# Sheet1.net
KiCad netlist of a schematic drawn in Altium Designer
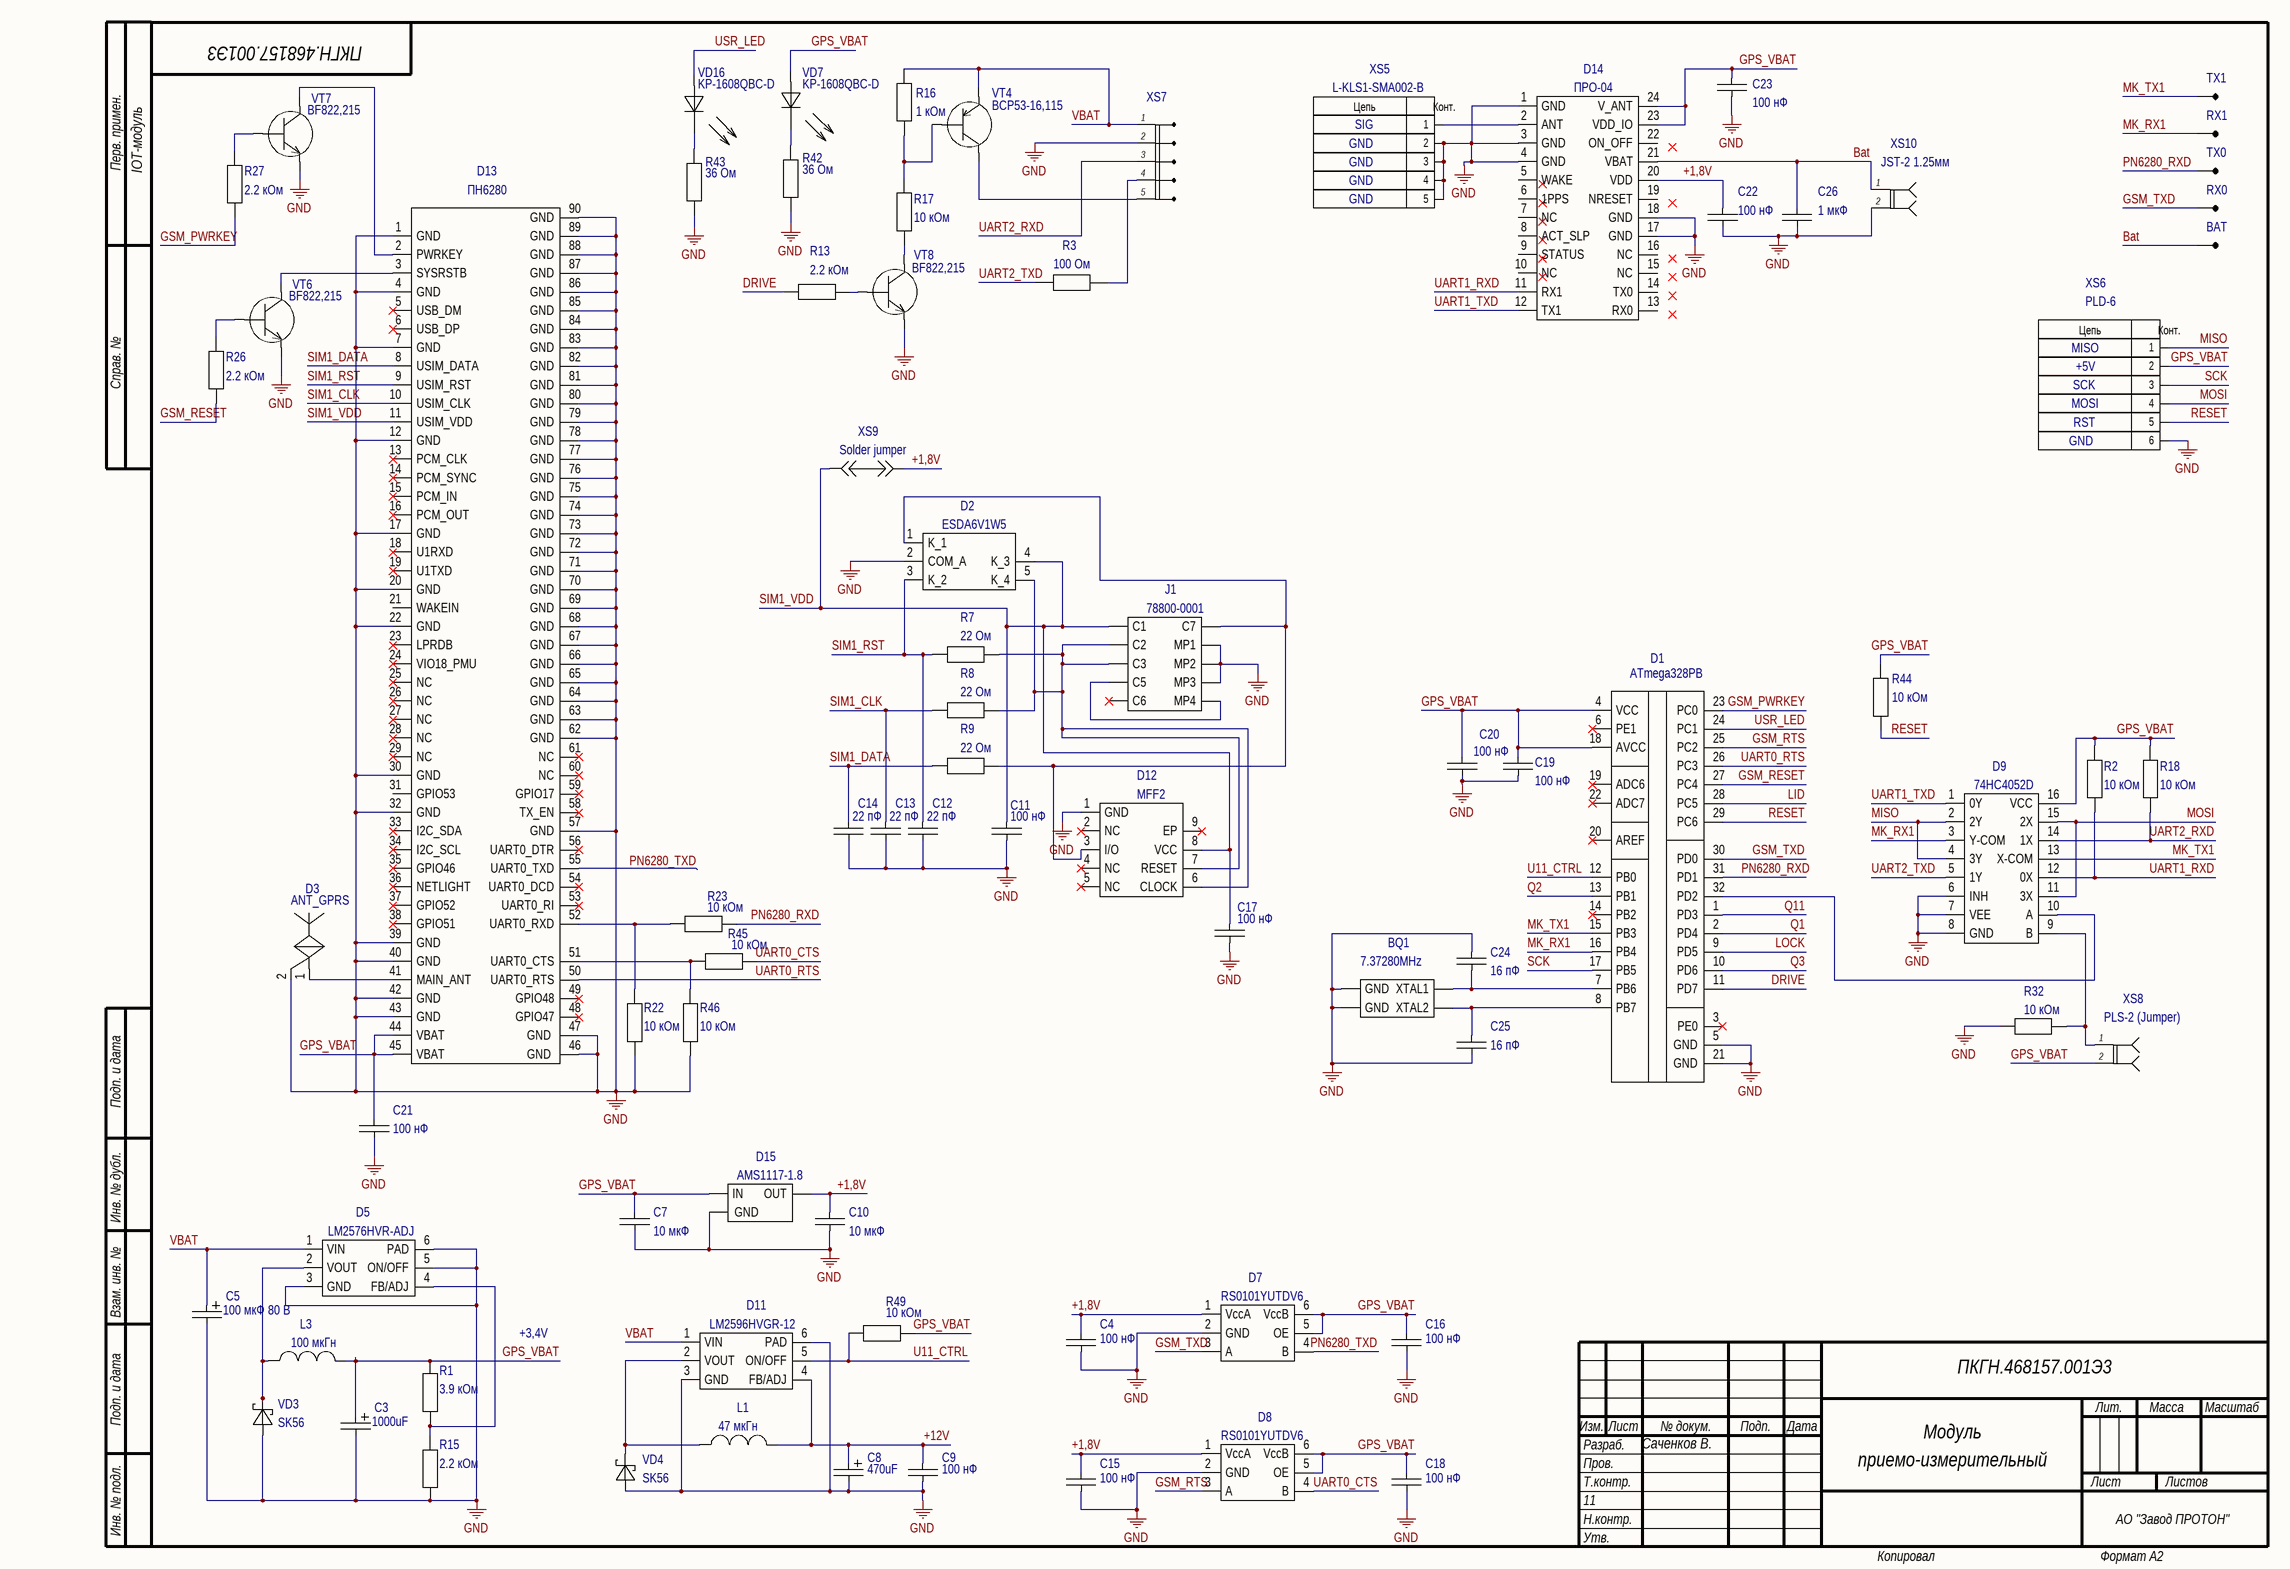
[diagram p0: Sheet1.SchDoc]

(export (version "E")
  (design (tool "Eeschema 10.0.6"))
  (components
    (comp (ref "BAT") (value "Pad") (footprint "PAD") (libsource (lib "Connectors") (part "Pad")))
    (comp (ref "BQ1")
      (value "7.37280MHz")
      (footprint "XTALL_KX-13")
      (description "https://www.elitan.ru/price/item348176")
      (libsource (lib "Own_lib") (part "XTALL_KX-13"))
    )
    (comp (ref "C3")
      (value "1000uF")
      (footprint "Own_lib:CP_SMD_BD10.0-L10.3_W10.3-LS11.0")
      (fields (field (name "TOLERANCE") "20%"))
      (libsource (lib "sch_RU") (part "CapPol"))
    )
    (comp (ref "C4")
      (value "100 нФ")
      (footprint "C_0603_(1608)")
      (fields (field (name "TOLERANCE") "10%"))
      (libsource (lib "sch_RU") (part "Cap"))
    )
    (comp (ref "C5")
      (value "100 мкФ 80 В")
      (footprint "CP_D12.5_H13.5")
      (fields (field (name "TOLERANCE") "20%"))
      (libsource (lib "sch_RU") (part "CapPol"))
    )
    (comp (ref "C7")
      (value "10 мкФ")
      (footprint "C_0603_(1608)")
      (fields (field (name "TOLERANCE") "20%"))
      (libsource (lib "Common_components") (part "C"))
    )
    (comp (ref "C8")
      (value "470uF")
      (footprint "Own_lib:CP_SMD_BD10.0-L10.3_W10.3-LS11.0")
      (fields (field (name "TOLERANCE") "20%"))
      (libsource (lib "sch_RU") (part "CapPol"))
    )
    (comp (ref "C9")
      (value "100 нФ")
      (footprint "C_0603_(1608)")
      (fields (field (name "TOLERANCE") "10%"))
      (libsource (lib "sch_RU") (part "Cap"))
    )
    (comp (ref "C10")
      (value "10 мкФ")
      (footprint "C_0603_(1608)")
      (fields (field (name "TOLERANCE") "20%"))
      (libsource (lib "Common_components") (part "C"))
    )
    (comp (ref "C11")
      (value "100 нФ")
      (footprint "C_0603_(1608)")
      (fields (field (name "TOLERANCE") "10%"))
      (libsource (lib "sch_RU") (part "Cap"))
    )
    (comp (ref "C12")
      (value "22 пФ")
      (footprint "C_0603_(1608)")
      (fields (field (name "TOLERANCE") "5%"))
      (libsource (lib "sch_RU") (part "Cap"))
    )
    (comp (ref "C13")
      (value "22 пФ")
      (footprint "C_0603_(1608)")
      (fields (field (name "TOLERANCE") "5%"))
      (libsource (lib "sch_RU") (part "Cap"))
    )
    (comp (ref "C14")
      (value "22 пФ")
      (footprint "C_0603_(1608)")
      (fields (field (name "TOLERANCE") "5%"))
      (libsource (lib "sch_RU") (part "Cap"))
    )
    (comp (ref "C15")
      (value "100 нФ")
      (footprint "C_0603_(1608)")
      (fields (field (name "TOLERANCE") "10%"))
      (libsource (lib "sch_RU") (part "Cap"))
    )
    (comp (ref "C16")
      (value "100 нФ")
      (footprint "C_0603_(1608)")
      (fields (field (name "TOLERANCE") "10%"))
      (libsource (lib "sch_RU") (part "Cap"))
    )
    (comp (ref "C17")
      (value "100 нФ")
      (footprint "C_0603_(1608)")
      (fields (field (name "TOLERANCE") "10%"))
      (libsource (lib "sch_RU") (part "Cap"))
    )
    (comp (ref "C18")
      (value "100 нФ")
      (footprint "C_0603_(1608)")
      (fields (field (name "TOLERANCE") "10%"))
      (libsource (lib "sch_RU") (part "Cap"))
    )
    (comp (ref "C19")
      (value "100 нФ")
      (footprint "C_0603_(1608)")
      (fields (field (name "TOLERANCE") "10%"))
      (libsource (lib "sch_RU") (part "Cap"))
    )
    (comp (ref "C20")
      (value "100 нФ")
      (footprint "C_0603_(1608)")
      (fields (field (name "TOLERANCE") "10%"))
      (libsource (lib "sch_RU") (part "Cap"))
    )
    (comp (ref "C21")
      (value "100 нФ")
      (footprint "C_0603_(1608)")
      (fields (field (name "TOLERANCE") "10%"))
      (libsource (lib "sch_RU") (part "Cap"))
    )
    (comp (ref "C22")
      (value "100 нФ")
      (footprint "C_0603_(1608)")
      (fields (field (name "TOLERANCE") "10%"))
      (libsource (lib "sch_RU") (part "Cap"))
    )
    (comp (ref "C23")
      (value "100 нФ")
      (footprint "C_0603_(1608)")
      (fields (field (name "TOLERANCE") "10%"))
      (libsource (lib "sch_RU") (part "Cap"))
    )
    (comp (ref "C24")
      (value "16 пФ")
      (footprint "C_0603_(1608)")
      (fields (field (name "TOLERANCE") "5%"))
      (libsource (lib "sch_RU") (part "Cap"))
    )
    (comp (ref "C25")
      (value "16 пФ")
      (footprint "C_0603_(1608)")
      (fields (field (name "TOLERANCE") "5%"))
      (libsource (lib "sch_RU") (part "Cap"))
    )
    (comp (ref "C26")
      (value "1 мкФ")
      (footprint "С_0805_(2012)")
      (fields (field (name "TOLERANCE") "10%"))
      (libsource (lib "sch_RU") (part "Cap"))
    )
    (comp (ref "D1")
      (value "ATmega328PB")
      (footprint "QFP80P900X900X120-32N")
      (libsource (lib "Own_lib") (part "ATmega328PB"))
    )
    (comp (ref "D2")
      (value "ESDA6V1W5")
      (footprint "SamacSys:SOT65P210X110-5N")
      (libsource (lib "Own_lib") (part "ESDA6V1W5"))
    )
    (comp (ref "D3")
      (value "ANT_GPRS")
      (footprint "ANT_GPRS")
      (description "PCB_ant")
      (libsource (lib "Own_lib") (part "ANT_GPRS"))
    )
    (comp (ref "D5")
      (value "LM2576HVR-ADJ")
      (footprint "Own_lib:TO-263-5")
      (libsource (lib "Own_lib") (part "LM2576HVR-ADJ"))
    )
    (comp (ref "D7")
      (value "RS0101YUTDV6")
      (footprint "DFN1.54x1.0-6L")
      (libsource (lib "Own_lib") (part "RS0101YUTDV6"))
    )
    (comp (ref "D8")
      (value "RS0101YUTDV6")
      (footprint "DFN1.54x1.0-6L")
      (libsource (lib "Own_lib") (part "RS0101YUTDV6"))
    )
    (comp (ref "D9")
      (value "74HC4052D")
      (footprint "SOIC127P600X175-16N")
      (libsource (lib "Own_lib") (part "74HC4052D"))
    )
    (comp (ref "D11")
      (value "LM2596HVGR-12")
      (footprint "Own_lib:TO-263-5")
      (libsource (lib "Own_lib") (part "LM2596HVGR-12"))
    )
    (comp (ref "D12")
      (value "MFF2")
      (footprint "SamacSys:SON127P600X500X90-9N-D")
      (libsource (lib "Own_lib") (part "MFF2"))
    )
    (comp (ref "D13")
      (value "ПН6280")
      (footprint "Own_lib:ПН6280")
      (libsource (lib "Own_lib") (part "ПН6280"))
    )
    (comp (ref "D14") (value "ПРО-04") (footprint "PRO-04_SMD") (libsource (lib "Own_lib") (part "PRO-04")))
    (comp (ref "D15")
      (value "AMS1117-1.8")
      (footprint "SOT-223(BCE)")
      (description "https://www.chipdip.ru/product/ams1117-1.8")
      (libsource (lib "Own_lib") (part "AMS1117-3.3"))
    )
    (comp (ref "J1") (value "78800-0001") (libsource (lib "Own_lib") (part "78800")))
    (comp (ref "L1")
      (value "47 мкГн")
      (footprint "Own_lib:B82477G4")
      (libsource (lib "Own_lib") (part "Inductor"))
    )
    (comp (ref "L3")
      (value "100 мкГн")
      (footprint "Own_lib:Inductor_SMD")
      (libsource (lib "Own_lib") (part "Inductor"))
    )
    (comp (ref "R1")
      (value "3.9 кОм")
      (footprint "R_0603_(1608)")
      (fields (field (name "TOLERANCE") "5%"))
      (libsource (lib "Own_lib") (part "R"))
    )
    (comp (ref "R2")
      (value "10 кОм")
      (footprint "R_0603_(1608)")
      (fields (field (name "TOLERANCE") "5%"))
      (libsource (lib "Own_lib") (part "R"))
    )
    (comp (ref "R3")
      (value "100 Ом")
      (footprint "R_0603_(1608)")
      (fields (field (name "TOLERANCE") "5%"))
      (libsource (lib "Common_components") (part "R"))
    )
    (comp (ref "R7")
      (value "22 Ом")
      (footprint "R_0603_(1608)")
      (fields (field (name "TOLERANCE") "5%"))
      (libsource (lib "") (part "R_1"))
    )
    (comp (ref "R8")
      (value "22 Ом")
      (footprint "R_0603_(1608)")
      (fields (field (name "TOLERANCE") "5%"))
      (libsource (lib "") (part "R_1"))
    )
    (comp (ref "R9")
      (value "22 Ом")
      (footprint "R_0603_(1608)")
      (fields (field (name "TOLERANCE") "5%"))
      (libsource (lib "") (part "R_1"))
    )
    (comp (ref "R13")
      (value "2.2 кОм")
      (footprint "R_0603_(1608)")
      (fields (field (name "TOLERANCE") "5%"))
      (libsource (lib "") (part "R_3"))
    )
    (comp (ref "R15")
      (value "2.2 кОм")
      (footprint "R_0603_(1608)")
      (fields (field (name "TOLERANCE") "5%"))
      (libsource (lib "Own_lib") (part "R"))
    )
    (comp (ref "R16")
      (value "1 кОм")
      (footprint "R_0603_(1608)")
      (fields (field (name "TOLERANCE") "5%"))
      (libsource (lib "Own_lib") (part "R"))
    )
    (comp (ref "R17")
      (value "10 кОм")
      (footprint "R_0603_(1608)")
      (fields (field (name "TOLERANCE") "5%"))
      (libsource (lib "Own_lib") (part "R"))
    )
    (comp (ref "R18")
      (value "10 кОм")
      (footprint "R_0603_(1608)")
      (fields (field (name "TOLERANCE") "5%"))
      (libsource (lib "Own_lib") (part "R"))
    )
    (comp (ref "R22")
      (value "10 кОм")
      (footprint "R_0603_(1608)")
      (fields (field (name "TOLERANCE") "5%"))
      (libsource (lib "Own_lib") (part "R"))
    )
    (comp (ref "R23")
      (value "10 кОм")
      (footprint "R_0603_(1608)")
      (fields (field (name "TOLERANCE") "5%"))
      (libsource (lib "") (part "R_1"))
    )
    (comp (ref "R26")
      (value "2.2 кОм")
      (footprint "R_0603_(1608)")
      (fields (field (name "TOLERANCE") "5%"))
      (libsource (lib "Own_lib") (part "R"))
    )
    (comp (ref "R27")
      (value "2.2 кОм")
      (footprint "R_0603_(1608)")
      (fields (field (name "TOLERANCE") "5%"))
      (libsource (lib "Own_lib") (part "R"))
    )
    (comp (ref "R32")
      (value "10 кОм")
      (footprint "R_0603_(1608)")
      (fields (field (name "TOLERANCE") "5%"))
      (libsource (lib "") (part "R_1"))
    )
    (comp (ref "R42")
      (value "36 Ом")
      (footprint "R_0603_(1608)")
      (fields (field (name "TOLERANCE") "5%"))
      (libsource (lib "Own_lib") (part "R"))
    )
    (comp (ref "R43")
      (value "36 Ом")
      (footprint "R_0603_(1608)")
      (fields (field (name "TOLERANCE") "5%"))
      (libsource (lib "Own_lib") (part "R"))
    )
    (comp (ref "R44")
      (value "10 кОм")
      (footprint "R_0603_(1608)")
      (fields (field (name "TOLERANCE") "5%"))
      (libsource (lib "") (part "R_2"))
    )
    (comp (ref "R45")
      (value "10 кОм")
      (footprint "R_0603_(1608)")
      (fields (field (name "TOLERANCE") "5%"))
      (libsource (lib "") (part "R_1"))
    )
    (comp (ref "R46")
      (value "10 кОм")
      (footprint "R_0603_(1608)")
      (fields (field (name "TOLERANCE") "5%"))
      (libsource (lib "Own_lib") (part "R"))
    )
    (comp (ref "R49")
      (value "10 кОм")
      (footprint "R_0603_(1608)")
      (fields (field (name "TOLERANCE") "5%"))
      (libsource (lib "") (part "R_1"))
    )
    (comp (ref "RX0") (value "Pad") (footprint "PAD") (libsource (lib "Connectors") (part "Pad")))
    (comp (ref "RX1") (value "Pad") (footprint "PAD") (libsource (lib "Connectors") (part "Pad")))
    (comp (ref "TX0") (value "Pad") (footprint "PAD") (libsource (lib "Connectors") (part "Pad")))
    (comp (ref "TX1") (value "Pad") (footprint "PAD") (libsource (lib "Connectors") (part "Pad")))
    (comp (ref "VD3")
      (value "SK56")
      (footprint "DIONM5236X261N")
      (description "https://www.chipdip.ru/product/sk56")
      (libsource (lib "sch_RU") (part "Schottky"))
    )
    (comp (ref "VD4")
      (value "SK56")
      (footprint "DIONM5236X261N")
      (description "https://www.chipdip.ru/product/sk56")
      (libsource (lib "sch_RU") (part "Schottky"))
    )
    (comp (ref "VD7")
      (value "KP-1608QBC-D")
      (footprint "SamacSys:KP1608QBCD")
      (libsource (lib "Own_lib") (part "LED"))
    )
    (comp (ref "VD16")
      (value "KP-1608QBC-D")
      (footprint "SamacSys:KP1608QBCD")
      (libsource (lib "Own_lib") (part "LED"))
    )
    (comp (ref "VT4")
      (value "BCP53-16,115")
      (footprint "SOT-223(BCE)")
      (description "https://www.chipdip.ru/product/bcp53-16-nxp")
      (libsource (lib "sch_RU") (part "TRANS-PNP"))
    )
    (comp (ref "VT6")
      (value "BF822,215")
      (footprint "SOT23-3")
      (description "https://www.chipdip.ru/product/bf822-215")
      (libsource (lib "sch_RU") (part "TRANS-NPN"))
    )
    (comp (ref "VT7")
      (value "BF822,215")
      (footprint "SOT23-3")
      (description "https://www.chipdip.ru/product/bf822-215")
      (libsource (lib "sch_RU") (part "TRANS-NPN"))
    )
    (comp (ref "VT8")
      (value "BF822,215")
      (footprint "SOT23-3")
      (description "https://www.chipdip.ru/product/bf822-215")
      (libsource (lib "sch_RU") (part "TRANS-NPN"))
    )
    (comp (ref "XS5")
      (value "L-KLS1-SMA002-B")
      (footprint "LKLS1SMA002B")
      (description "https://www.chipdip.ru/product/kls1-sma002-b-sma-jr")
      (libsource (lib "Own_lib") (part "PLS_5"))
    )
    (comp (ref "XS6")
      (value "PLD-6")
      (footprint "connector:PLD-6")
      (libsource (lib "Own_lib") (part "PLS_6"))
    )
    (comp (ref "XS7")
      (value "Pad 1x5")
      (footprint "PLS-5(NO_3D)")
      (libsource (lib "Connectors") (part "Pad 1x5"))
    )
    (comp (ref "XS8")
      (value "PLS-2 (Jumper)")
      (footprint "PLS-2")
      (libsource (lib "Connectors") (part "XS2"))
    )
    (comp (ref "XS9")
      (value "Solder jumper")
      (footprint "Solder_Jumper")
      (libsource (lib "Own_lib") (part "Jumper_2"))
    )
    (comp (ref "XS10")
      (value "JST-2 1.25мм")
      (footprint "JST-2_1.25")
      (description "https://www.chipdip.ru/product0/9000808758")
      (libsource (lib "Connectors") (part "XS2"))
    )
  )
  (nets
    (net (code "1") (name "/+1,8V") (class "Default")
      (node (ref "C10") (pin "1") (pinfunction "1_1") (pintype "passive"))
      (node (ref "C15") (pin "2") (pinfunction "2_2") (pintype "passive"))
      (node (ref "C22") (pin "2") (pinfunction "2_2") (pintype "passive"))
      (node (ref "C4") (pin "2") (pinfunction "2_2") (pintype "passive"))
      (node (ref "D14") (pin "20") (pinfunction "VDD_20") (pintype "passive"))
      (node (ref "D15") (pin "2") (pinfunction "OUT_2") (pintype "passive"))
      (node (ref "D7") (pin "1") (pinfunction "VccA_1") (pintype "passive"))
      (node (ref "D8") (pin "1") (pinfunction "VccA_1") (pintype "passive"))
      (node (ref "XS9") (pin "2") (pinfunction "2_2") (pintype "passive"))
    )
    (net (code "2") (name "/+12V") (class "Default")
      (node (ref "C8") (pin "1") (pinfunction "1_1") (pintype "passive"))
      (node (ref "C9") (pin "2") (pinfunction "2_2") (pintype "passive"))
      (node (ref "D11") (pin "4") (pinfunction "FB/ADJ_4") (pintype "passive"))
      (node (ref "L1") (pin "2") (pinfunction "2_2") (pintype "passive"))
    )
    (net (code "3") (name "/Bat") (class "Default")
      (node (ref "BAT") (pin "1") (pinfunction "1_1") (pintype "passive"))
      (node (ref "C26") (pin "2") (pinfunction "2_2") (pintype "passive"))
      (node (ref "D14") (pin "21") (pinfunction "VBAT_21") (pintype "passive"))
      (node (ref "XS10") (pin "1") (pinfunction "1_1") (pintype "passive"))
    )
    (net (code "4") (name "/DRIVE") (class "Default")
      (node (ref "D1") (pin "11") (pinfunction "PD7_11") (pintype "passive"))
      (node (ref "R13") (pin "1") (pinfunction "1_1") (pintype "passive"))
    )
    (net (code "5") (name "/GPS_VBAT") (class "Default")
      (node (ref "C16") (pin "2") (pinfunction "2_2") (pintype "passive"))
      (node (ref "C18") (pin "2") (pinfunction "2_2") (pintype "passive"))
      (node (ref "C19") (pin "2") (pinfunction "2_2") (pintype "passive"))
      (node (ref "C20") (pin "2") (pinfunction "2_2") (pintype "passive"))
      (node (ref "C21") (pin "2") (pinfunction "2_2") (pintype "passive"))
      (node (ref "C23") (pin "2") (pinfunction "2_2") (pintype "passive"))
      (node (ref "C3") (pin "1") (pinfunction "1_1") (pintype "passive"))
      (node (ref "C7") (pin "1") (pinfunction "1_1") (pintype "passive"))
      (node (ref "D1") (pin "18") (pinfunction "AVCC_18") (pintype "passive"))
      (node (ref "D1") (pin "4") (pinfunction "VCC_4") (pintype "passive"))
      (node (ref "D13") (pin "44") (pinfunction "VBAT_44") (pintype "passive"))
      (node (ref "D13") (pin "45") (pinfunction "VBAT_45") (pintype "passive"))
      (node (ref "D14") (pin "23") (pinfunction "VDD_IO_23") (pintype "passive"))
      (node (ref "D14") (pin "24") (pinfunction "V_ANT_24") (pintype "passive"))
      (node (ref "D15") (pin "3") (pinfunction "IN_3") (pintype "passive"))
      (node (ref "D7") (pin "5") (pinfunction "OE_5") (pintype "passive"))
      (node (ref "D7") (pin "6") (pinfunction "VccB_6") (pintype "passive"))
      (node (ref "D8") (pin "5") (pinfunction "OE_5") (pintype "passive"))
      (node (ref "D8") (pin "6") (pinfunction "VccB_6") (pintype "passive"))
      (node (ref "D9") (pin "16") (pinfunction "VCC_16") (pintype "passive"))
      (node (ref "L3") (pin "2") (pinfunction "2_2") (pintype "passive"))
      (node (ref "R1") (pin "2") (pinfunction "2_2") (pintype "passive"))
      (node (ref "R18") (pin "2") (pinfunction "2_2") (pintype "passive"))
      (node (ref "R2") (pin "2") (pinfunction "2_2") (pintype "passive"))
      (node (ref "R44") (pin "1") (pinfunction "1_1") (pintype "passive"))
      (node (ref "R49") (pin "1") (pinfunction "1_1") (pintype "passive"))
      (node (ref "VD7") (pin "1") (pinfunction "A_1") (pintype "passive"))
      (node (ref "XS6") (pin "2") (pinfunction "2_2") (pintype "passive"))
      (node (ref "XS8") (pin "2") (pinfunction "2_2") (pintype "passive"))
    )
    (net (code "6") (name "/GSM_PWRKEY") (class "Default")
      (node (ref "D1") (pin "23") (pinfunction "PC0_23") (pintype "passive"))
      (node (ref "R27") (pin "1") (pinfunction "1_1") (pintype "passive"))
    )
    (net (code "7") (name "/GSM_RESET") (class "Default")
      (node (ref "D1") (pin "27") (pinfunction "PC4_27") (pintype "passive"))
      (node (ref "R26") (pin "1") (pinfunction "1_1") (pintype "passive"))
    )
    (net (code "8") (name "/GSM_RTS") (class "Default")
      (node (ref "D1") (pin "25") (pinfunction "PC2_25") (pintype "passive"))
      (node (ref "D8") (pin "3") (pinfunction "A_3") (pintype "passive"))
    )
    (net (code "9") (name "/GSM_TXD") (class "Default")
      (node (ref "D1") (pin "30") (pinfunction "PD0_30") (pintype "passive"))
      (node (ref "D7") (pin "3") (pinfunction "A_3") (pintype "passive"))
      (node (ref "RX0") (pin "1") (pinfunction "1_1") (pintype "passive"))
    )
    (net (code "10") (name "/LID") (class "Default")
      (node (ref "D1") (pin "28") (pinfunction "PC5_28") (pintype "passive"))
    )
    (net (code "11") (name "/LOCK") (class "Default")
      (node (ref "D1") (pin "9") (pinfunction "PD5_9") (pintype "passive"))
    )
    (net (code "12") (name "/MISO") (class "Default")
      (node (ref "D9") (pin "2") (pinfunction "2Y_2") (pintype "passive"))
      (node (ref "D9") (pin "4") (pinfunction "3Y_4") (pintype "passive"))
      (node (ref "XS6") (pin "1") (pinfunction "1_1") (pintype "passive"))
    )
    (net (code "13") (name "/MK_RX1") (class "Default")
      (node (ref "D1") (pin "16") (pinfunction "PB4_16") (pintype "passive"))
      (node (ref "D9") (pin "3") (pinfunction "Y-COM_3") (pintype "passive"))
      (node (ref "RX1") (pin "1") (pinfunction "1_1") (pintype "passive"))
    )
    (net (code "14") (name "/MK_TX1") (class "Default")
      (node (ref "D1") (pin "15") (pinfunction "PB3_15") (pintype "passive"))
      (node (ref "D9") (pin "13") (pinfunction "X-COM_13") (pintype "passive"))
      (node (ref "TX1") (pin "1") (pinfunction "1_1") (pintype "passive"))
    )
    (net (code "15") (name "/MOSI") (class "Default")
      (node (ref "D9") (pin "11") (pinfunction "3X_11") (pintype "passive"))
      (node (ref "D9") (pin "15") (pinfunction "2X_15") (pintype "passive"))
      (node (ref "XS6") (pin "4") (pinfunction "4_4") (pintype "passive"))
    )
    (net (code "16") (name "/PN6280_RXD") (class "Default")
      (node (ref "D1") (pin "31") (pinfunction "PD1_31") (pintype "passive"))
      (node (ref "R23") (pin "1") (pinfunction "1_1") (pintype "passive"))
      (node (ref "TX0") (pin "1") (pinfunction "1_1") (pintype "passive"))
    )
    (net (code "17") (name "/PN6280_TXD") (class "Default")
      (node (ref "D13") (pin "55") (pinfunction "UART0_TXD_55") (pintype "passive"))
      (node (ref "D7") (pin "4") (pinfunction "B_4") (pintype "passive"))
    )
    (net (code "18") (name "/Q1") (class "Default")
      (node (ref "D1") (pin "2") (pinfunction "PD4_2") (pintype "passive"))
    )
    (net (code "19") (name "/Q2") (class "Default")
      (node (ref "D1") (pin "13") (pinfunction "PB1_13") (pintype "passive"))
    )
    (net (code "20") (name "/Q3") (class "Default")
      (node (ref "D1") (pin "10") (pinfunction "PD6_10") (pintype "passive"))
    )
    (net (code "21") (name "/Q11") (class "Default")
      (node (ref "D1") (pin "1") (pinfunction "PD3_1") (pintype "passive"))
    )
    (net (code "22") (name "/RESET") (class "Default")
      (node (ref "D1") (pin "29") (pinfunction "PC6_29") (pintype "passive"))
      (node (ref "R44") (pin "2") (pinfunction "2_2") (pintype "passive"))
      (node (ref "XS6") (pin "5") (pinfunction "5_5") (pintype "passive"))
    )
    (net (code "23") (name "/SCK") (class "Default")
      (node (ref "D1") (pin "17") (pinfunction "PB5_17") (pintype "passive"))
      (node (ref "XS6") (pin "3") (pinfunction "3_3") (pintype "passive"))
    )
    (net (code "24") (name "/SIM1_CLK") (class "Default")
      (node (ref "C13") (pin "2") (pinfunction "2_2") (pintype "passive"))
      (node (ref "D13") (pin "10") (pinfunction "USIM_CLK_10") (pintype "passive"))
      (node (ref "R8") (pin "2") (pinfunction "2_2") (pintype "passive"))
    )
    (net (code "25") (name "/SIM1_DATA") (class "Default")
      (node (ref "C14") (pin "2") (pinfunction "2_2") (pintype "passive"))
      (node (ref "D13") (pin "8") (pinfunction "USIM_DATA_8") (pintype "passive"))
      (node (ref "R9") (pin "2") (pinfunction "2_2") (pintype "passive"))
    )
    (net (code "26") (name "/SIM1_RST") (class "Default")
      (node (ref "C12") (pin "2") (pinfunction "2_2") (pintype "passive"))
      (node (ref "D13") (pin "9") (pinfunction "USIM_RST_9") (pintype "passive"))
      (node (ref "D2") (pin "3") (pinfunction "K_2_3") (pintype "passive"))
      (node (ref "R7") (pin "2") (pinfunction "2_2") (pintype "passive"))
    )
    (net (code "27") (name "/SIM1_VDD") (class "Default")
      (node (ref "C11") (pin "2") (pinfunction "2_2") (pintype "passive"))
      (node (ref "C17") (pin "2") (pinfunction "2_2") (pintype "passive"))
      (node (ref "D12") (pin "8") (pinfunction "VCC_8") (pintype "passive"))
      (node (ref "D13") (pin "11") (pinfunction "USIM_VDD_11") (pintype "passive"))
      (node (ref "D2") (pin "4") (pinfunction "K_3_4") (pintype "passive"))
      (node (ref "J1") (pin "C1") (pinfunction "C1_C1") (pintype "passive"))
      (node (ref "XS9") (pin "1") (pinfunction "1_1") (pintype "passive"))
    )
    (net (code "28") (name "/U11_CTRL") (class "Default")
      (node (ref "D1") (pin "12") (pinfunction "PB0_12") (pintype "passive"))
      (node (ref "D11") (pin "5") (pinfunction "ON/OFF_5") (pintype "passive"))
      (node (ref "R49") (pin "2") (pinfunction "2_2") (pintype "passive"))
    )
    (net (code "29") (name "/UART0_CTS") (class "Default")
      (node (ref "D8") (pin "4") (pinfunction "B_4") (pintype "passive"))
      (node (ref "R45") (pin "1") (pinfunction "1_1") (pintype "passive"))
    )
    (net (code "30") (name "/UART0_RTS") (class "Default")
      (node (ref "D1") (pin "26") (pinfunction "PC3_26") (pintype "passive"))
      (node (ref "D13") (pin "50") (pinfunction "UART0_RTS_50") (pintype "passive"))
    )
    (net (code "31") (name "/UART1_RXD") (class "Default")
      (node (ref "D14") (pin "11") (pinfunction "RX1_11") (pintype "passive"))
      (node (ref "D9") (pin "12") (pinfunction "0X_12") (pintype "passive"))
      (node (ref "R2") (pin "1") (pinfunction "1_1") (pintype "passive"))
    )
    (net (code "32") (name "/UART1_TXD") (class "Default")
      (node (ref "D14") (pin "12") (pinfunction "TX1_12") (pintype "passive"))
      (node (ref "D9") (pin "1") (pinfunction "0Y_1") (pintype "passive"))
    )
    (net (code "33") (name "/UART2_RXD") (class "Default")
      (node (ref "D9") (pin "14") (pinfunction "1X_14") (pintype "passive"))
      (node (ref "R18") (pin "1") (pinfunction "1_1") (pintype "passive"))
      (node (ref "XS7") (pin "3") (pinfunction "3_3") (pintype "passive"))
    )
    (net (code "34") (name "/UART2_TXD") (class "Default")
      (node (ref "D9") (pin "5") (pinfunction "1Y_5") (pintype "passive"))
      (node (ref "R3") (pin "1") (pinfunction "1_1") (pintype "passive"))
    )
    (net (code "35") (name "/USR_LED") (class "Default")
      (node (ref "D1") (pin "24") (pinfunction "PC1_24") (pintype "passive"))
      (node (ref "VD16") (pin "1") (pinfunction "A_1") (pintype "passive"))
    )
    (net (code "36") (name "/VBAT") (class "Default")
      (node (ref "C5") (pin "1") (pinfunction "1_1") (pintype "passive"))
      (node (ref "D11") (pin "1") (pinfunction "VIN_1") (pintype "passive"))
      (node (ref "D5") (pin "1") (pinfunction "VIN_1") (pintype "passive"))
      (node (ref "R16") (pin "2") (pinfunction "2_2") (pintype "passive"))
      (node (ref "VT4") (pin "3") (pinfunction "E_3") (pintype "passive"))
      (node (ref "XS7") (pin "1") (pinfunction "1_1") (pintype "passive"))
    )
    (net (code "37") (name "GND") (class "Default")
      (node (ref "BQ1") (pin "2") (pinfunction "GND_2") (pintype "passive"))
      (node (ref "BQ1") (pin "4") (pinfunction "GND_4") (pintype "passive"))
      (node (ref "C10") (pin "2") (pinfunction "2_2") (pintype "passive"))
      (node (ref "C11") (pin "1") (pinfunction "1_1") (pintype "passive"))
      (node (ref "C12") (pin "1") (pinfunction "1_1") (pintype "passive"))
      (node (ref "C13") (pin "1") (pinfunction "1_1") (pintype "passive"))
      (node (ref "C14") (pin "1") (pinfunction "1_1") (pintype "passive"))
      (node (ref "C15") (pin "1") (pinfunction "1_1") (pintype "passive"))
      (node (ref "C16") (pin "1") (pinfunction "1_1") (pintype "passive"))
      (node (ref "C17") (pin "1") (pinfunction "1_1") (pintype "passive"))
      (node (ref "C18") (pin "1") (pinfunction "1_1") (pintype "passive"))
      (node (ref "C19") (pin "1") (pinfunction "1_1") (pintype "passive"))
      (node (ref "C20") (pin "1") (pinfunction "1_1") (pintype "passive"))
      (node (ref "C21") (pin "1") (pinfunction "1_1") (pintype "passive"))
      (node (ref "C22") (pin "1") (pinfunction "1_1") (pintype "passive"))
      (node (ref "C23") (pin "1") (pinfunction "1_1") (pintype "passive"))
      (node (ref "C24") (pin "2") (pinfunction "2_2") (pintype "passive"))
      (node (ref "C25") (pin "1") (pinfunction "1_1") (pintype "passive"))
      (node (ref "C26") (pin "1") (pinfunction "1_1") (pintype "passive"))
      (node (ref "C3") (pin "2") (pinfunction "2_2") (pintype "passive"))
      (node (ref "C4") (pin "1") (pinfunction "1_1") (pintype "passive"))
      (node (ref "C5") (pin "2") (pinfunction "2_2") (pintype "passive"))
      (node (ref "C7") (pin "2") (pinfunction "2_2") (pintype "passive"))
      (node (ref "C8") (pin "2") (pinfunction "2_2") (pintype "passive"))
      (node (ref "C9") (pin "1") (pinfunction "1_1") (pintype "passive"))
      (node (ref "D1") (pin "21") (pinfunction "GND_21") (pintype "passive"))
      (node (ref "D1") (pin "5") (pinfunction "GND_5") (pintype "passive"))
      (node (ref "D11") (pin "3") (pinfunction "GND_3") (pintype "passive"))
      (node (ref "D11") (pin "6") (pinfunction "PAD_6") (pintype "passive"))
      (node (ref "D12") (pin "1") (pinfunction "GND_1") (pintype "passive"))
      (node (ref "D13") (pin "1") (pinfunction "GND_1") (pintype "passive"))
      (node (ref "D13") (pin "12") (pinfunction "GND_12") (pintype "passive"))
      (node (ref "D13") (pin "17") (pinfunction "GND_17") (pintype "passive"))
      (node (ref "D13") (pin "20") (pinfunction "GND_20") (pintype "passive"))
      (node (ref "D13") (pin "22") (pinfunction "GND_22") (pintype "passive"))
      (node (ref "D13") (pin "30") (pinfunction "GND_30") (pintype "passive"))
      (node (ref "D13") (pin "32") (pinfunction "GND_32") (pintype "passive"))
      (node (ref "D13") (pin "39") (pinfunction "GND_39") (pintype "passive"))
      (node (ref "D13") (pin "4") (pinfunction "GND_4") (pintype "passive"))
      (node (ref "D13") (pin "40") (pinfunction "GND_40") (pintype "passive"))
      (node (ref "D13") (pin "42") (pinfunction "GND_42") (pintype "passive"))
      (node (ref "D13") (pin "43") (pinfunction "GND_43") (pintype "passive"))
      (node (ref "D13") (pin "46") (pinfunction "GND_46") (pintype "passive"))
      (node (ref "D13") (pin "47") (pinfunction "GND_47") (pintype "passive"))
      (node (ref "D13") (pin "57") (pinfunction "GND_57") (pintype "passive"))
      (node (ref "D13") (pin "62") (pinfunction "GND_62") (pintype "passive"))
      (node (ref "D13") (pin "63") (pinfunction "GND_63") (pintype "passive"))
      (node (ref "D13") (pin "64") (pinfunction "GND_64") (pintype "passive"))
      (node (ref "D13") (pin "65") (pinfunction "GND_65") (pintype "passive"))
      (node (ref "D13") (pin "66") (pinfunction "GND_66") (pintype "passive"))
      (node (ref "D13") (pin "67") (pinfunction "GND_67") (pintype "passive"))
      (node (ref "D13") (pin "68") (pinfunction "GND_68") (pintype "passive"))
      (node (ref "D13") (pin "69") (pinfunction "GND_69") (pintype "passive"))
      (node (ref "D13") (pin "7") (pinfunction "GND_7") (pintype "passive"))
      (node (ref "D13") (pin "70") (pinfunction "GND_70") (pintype "passive"))
      (node (ref "D13") (pin "71") (pinfunction "GND_71") (pintype "passive"))
      (node (ref "D13") (pin "72") (pinfunction "GND_72") (pintype "passive"))
      (node (ref "D13") (pin "73") (pinfunction "GND_73") (pintype "passive"))
      (node (ref "D13") (pin "74") (pinfunction "GND_74") (pintype "passive"))
      (node (ref "D13") (pin "75") (pinfunction "GND_75") (pintype "passive"))
      (node (ref "D13") (pin "76") (pinfunction "GND_76") (pintype "passive"))
      (node (ref "D13") (pin "77") (pinfunction "GND_77") (pintype "passive"))
      (node (ref "D13") (pin "78") (pinfunction "GND_78") (pintype "passive"))
      (node (ref "D13") (pin "79") (pinfunction "GND_79") (pintype "passive"))
      (node (ref "D13") (pin "80") (pinfunction "GND_80") (pintype "passive"))
      (node (ref "D13") (pin "81") (pinfunction "GND_81") (pintype "passive"))
      (node (ref "D13") (pin "82") (pinfunction "GND_82") (pintype "passive"))
      (node (ref "D13") (pin "83") (pinfunction "GND_83") (pintype "passive"))
      (node (ref "D13") (pin "84") (pinfunction "GND_84") (pintype "passive"))
      (node (ref "D13") (pin "85") (pinfunction "GND_85") (pintype "passive"))
      (node (ref "D13") (pin "86") (pinfunction "GND_86") (pintype "passive"))
      (node (ref "D13") (pin "87") (pinfunction "GND_87") (pintype "passive"))
      (node (ref "D13") (pin "88") (pinfunction "GND_88") (pintype "passive"))
      (node (ref "D13") (pin "89") (pinfunction "GND_89") (pintype "passive"))
      (node (ref "D13") (pin "90") (pinfunction "GND_90") (pintype "passive"))
      (node (ref "D14") (pin "1") (pinfunction "GND_1") (pintype "passive"))
      (node (ref "D14") (pin "17") (pinfunction "GND_17") (pintype "passive"))
      (node (ref "D14") (pin "18") (pinfunction "GND_18") (pintype "passive"))
      (node (ref "D14") (pin "3") (pinfunction "GND_3") (pintype "passive"))
      (node (ref "D14") (pin "4") (pinfunction "GND_4") (pintype "passive"))
      (node (ref "D15") (pin "1") (pinfunction "GND_1") (pintype "passive"))
      (node (ref "D2") (pin "2") (pinfunction "COM_A_2") (pintype "passive"))
      (node (ref "D3") (pin "2") (pinfunction "GND_2") (pintype "passive"))
      (node (ref "D5") (pin "3") (pinfunction "GND_3") (pintype "passive"))
      (node (ref "D5") (pin "5") (pinfunction "ON/OFF_5") (pintype "passive"))
      (node (ref "D5") (pin "6") (pinfunction "PAD_6") (pintype "passive"))
      (node (ref "D7") (pin "2") (pinfunction "GND_2") (pintype "passive"))
      (node (ref "D8") (pin "2") (pinfunction "GND_2") (pintype "passive"))
      (node (ref "D9") (pin "6") (pinfunction "INH_6") (pintype "passive"))
      (node (ref "D9") (pin "7") (pinfunction "VEE_7") (pintype "passive"))
      (node (ref "D9") (pin "8") (pinfunction "GND_8") (pintype "passive"))
      (node (ref "J1") (pin "MP1") (pinfunction "MP1_MP1") (pintype "passive"))
      (node (ref "J1") (pin "MP2") (pinfunction "MP2_MP2") (pintype "passive"))
      (node (ref "J1") (pin "MP3") (pinfunction "MP3_MP3") (pintype "passive"))
      (node (ref "R15") (pin "1") (pinfunction "1_1") (pintype "passive"))
      (node (ref "R22") (pin "1") (pinfunction "1_1") (pintype "passive"))
      (node (ref "R32") (pin "2") (pinfunction "2_2") (pintype "passive"))
      (node (ref "R42") (pin "1") (pinfunction "1_1") (pintype "passive"))
      (node (ref "R43") (pin "1") (pinfunction "1_1") (pintype "passive"))
      (node (ref "R46") (pin "1") (pinfunction "1_1") (pintype "passive"))
      (node (ref "VD3") (pin "2") (pinfunction "2_2") (pintype "passive"))
      (node (ref "VD4") (pin "2") (pinfunction "2_2") (pintype "passive"))
      (node (ref "VT6") (pin "2") (pinfunction "E_2") (pintype "passive"))
      (node (ref "VT7") (pin "2") (pinfunction "E_2") (pintype "passive"))
      (node (ref "VT8") (pin "2") (pinfunction "E_2") (pintype "passive"))
      (node (ref "XS10") (pin "2") (pinfunction "2_2") (pintype "passive"))
      (node (ref "XS5") (pin "2") (pinfunction "2_2") (pintype "passive"))
      (node (ref "XS5") (pin "3") (pinfunction "3_3") (pintype "passive"))
      (node (ref "XS5") (pin "4") (pinfunction "4_4") (pintype "passive"))
      (node (ref "XS5") (pin "5") (pinfunction "5_5") (pintype "passive"))
      (node (ref "XS6") (pin "6") (pinfunction "6_6") (pintype "passive"))
      (node (ref "XS7") (pin "2") (pinfunction "2_2") (pintype "passive"))
    )
    (net (code "38") (name "Net-(BQ1-XTAL1)") (class "Default")
      (node (ref "BQ1") (pin "1") (pinfunction "XTAL1_1") (pintype "passive"))
      (node (ref "C24") (pin "1") (pinfunction "1_1") (pintype "passive"))
      (node (ref "D1") (pin "7") (pinfunction "PB6_7") (pintype "passive"))
    )
    (net (code "39") (name "Net-(BQ1-XTAL2)") (class "Default")
      (node (ref "BQ1") (pin "3") (pinfunction "XTAL2_3") (pintype "passive"))
      (node (ref "C25") (pin "2") (pinfunction "2_2") (pintype "passive"))
      (node (ref "D1") (pin "8") (pinfunction "PB7_8") (pintype "passive"))
    )
    (net (code "40") (name "Net-(D1-PD2)") (class "Default")
      (node (ref "D1") (pin "32") (pinfunction "PD2_32") (pintype "passive"))
      (node (ref "D9") (pin "10") (pinfunction "A_10") (pintype "passive"))
    )
    (net (code "41") (name "Net-(D5-FB{slash}ADJ)") (class "Default")
      (node (ref "D5") (pin "4") (pinfunction "FB/ADJ_4") (pintype "passive"))
      (node (ref "R1") (pin "1") (pinfunction "1_1") (pintype "passive"))
      (node (ref "R15") (pin "2") (pinfunction "2_2") (pintype "passive"))
    )
    (net (code "42") (name "Net-(D5-VOUT)") (class "Default")
      (node (ref "D5") (pin "2") (pinfunction "VOUT_2") (pintype "passive"))
      (node (ref "L3") (pin "1") (pinfunction "1_1") (pintype "passive"))
      (node (ref "VD3") (pin "1") (pinfunction "1_1") (pintype "passive"))
    )
    (net (code "43") (name "Net-(D9-B)") (class "Default")
      (node (ref "D9") (pin "9") (pinfunction "B_9") (pintype "passive"))
      (node (ref "R32") (pin "1") (pinfunction "1_1") (pintype "passive"))
      (node (ref "XS8") (pin "1") (pinfunction "1_1") (pintype "passive"))
    )
    (net (code "44") (name "Net-(D11-VOUT)") (class "Default")
      (node (ref "D11") (pin "2") (pinfunction "VOUT_2") (pintype "passive"))
      (node (ref "L1") (pin "1") (pinfunction "1_1") (pintype "passive"))
      (node (ref "VD4") (pin "1") (pinfunction "1_1") (pintype "passive"))
    )
    (net (code "45") (name "Net-(D12-CLOCK)") (class "Default")
      (node (ref "D12") (pin "6") (pinfunction "CLOCK_6") (pintype "passive"))
      (node (ref "D12") (pin "7") (pinfunction "RESET_7") (pintype "passive"))
      (node (ref "D2") (pin "5") (pinfunction "K_4_5") (pintype "passive"))
      (node (ref "J1") (pin "C2") (pinfunction "C2_C2") (pintype "passive"))
      (node (ref "J1") (pin "C3") (pinfunction "C3_C3") (pintype "passive"))
      (node (ref "R7") (pin "1") (pinfunction "1_1") (pintype "passive"))
      (node (ref "R8") (pin "1") (pinfunction "1_1") (pintype "passive"))
    )
    (net (code "46") (name "Net-(D12-I{slash}O)") (class "Default")
      (node (ref "D12") (pin "3") (pinfunction "I/O_3") (pintype "passive"))
      (node (ref "D2") (pin "1") (pinfunction "K_1_1") (pintype "passive"))
      (node (ref "J1") (pin "C7") (pinfunction "C7_C7") (pintype "passive"))
      (node (ref "R9") (pin "1") (pinfunction "1_1") (pintype "passive"))
    )
    (net (code "47") (name "Net-(D13-MAIN_ANT)") (class "Default")
      (node (ref "D13") (pin "41") (pinfunction "MAIN_ANT_41") (pintype "passive"))
      (node (ref "D3") (pin "1") (pinfunction "NET_1") (pintype "passive"))
    )
    (net (code "48") (name "Net-(D13-PWRKEY)") (class "Default")
      (node (ref "D13") (pin "2") (pinfunction "PWRKEY_2") (pintype "passive"))
      (node (ref "VT7") (pin "3") (pinfunction "C_3") (pintype "passive"))
    )
    (net (code "49") (name "Net-(D13-SYSRSTB)") (class "Default")
      (node (ref "D13") (pin "3") (pinfunction "SYSRSTB_3") (pintype "passive"))
      (node (ref "VT6") (pin "3") (pinfunction "C_3") (pintype "passive"))
    )
    (net (code "50") (name "Net-(D13-UART0_CTS)") (class "Default")
      (node (ref "D13") (pin "51") (pinfunction "UART0_CTS_51") (pintype "passive"))
      (node (ref "R45") (pin "2") (pinfunction "2_2") (pintype "passive"))
      (node (ref "R46") (pin "2") (pinfunction "2_2") (pintype "passive"))
    )
    (net (code "51") (name "Net-(D13-UART0_RXD)") (class "Default")
      (node (ref "D13") (pin "52") (pinfunction "UART0_RXD_52") (pintype "passive"))
      (node (ref "R22") (pin "2") (pinfunction "2_2") (pintype "passive"))
      (node (ref "R23") (pin "2") (pinfunction "2_2") (pintype "passive"))
    )
    (net (code "52") (name "Net-(D14-ANT)") (class "Default")
      (node (ref "D14") (pin "2") (pinfunction "ANT_2") (pintype "passive"))
      (node (ref "XS5") (pin "1") (pinfunction "1_1") (pintype "passive"))
    )
    (net (code "53") (name "Net-(J1-PadC5)") (class "Default")
      (node (ref "J1") (pin "C5") (pinfunction "C5_C5") (pintype "passive"))
      (node (ref "J1") (pin "MP4") (pinfunction "MP4_MP4") (pintype "passive"))
    )
    (net (code "54") (name "Net-(R3-Pad2)") (class "Default")
      (node (ref "R3") (pin "2") (pinfunction "2_2") (pintype "passive"))
      (node (ref "XS7") (pin "4") (pinfunction "4_4") (pintype "passive"))
    )
    (net (code "55") (name "Net-(VD7-C)") (class "Default")
      (node (ref "R42") (pin "2") (pinfunction "2_2") (pintype "passive"))
      (node (ref "VD7") (pin "2") (pinfunction "C_2") (pintype "passive"))
    )
    (net (code "56") (name "Net-(VD16-C)") (class "Default")
      (node (ref "R43") (pin "2") (pinfunction "2_2") (pintype "passive"))
      (node (ref "VD16") (pin "2") (pinfunction "C_2") (pintype "passive"))
    )
    (net (code "57") (name "Net-(VT4-B)") (class "Default")
      (node (ref "R16") (pin "1") (pinfunction "1_1") (pintype "passive"))
      (node (ref "R17") (pin "2") (pinfunction "2_2") (pintype "passive"))
      (node (ref "VT4") (pin "1") (pinfunction "B_1") (pintype "passive"))
    )
    (net (code "58") (name "Net-(VT4-C)") (class "Default")
      (node (ref "VT4") (pin "2") (pinfunction "C_2") (pintype "passive"))
      (node (ref "XS7") (pin "5") (pinfunction "5_5") (pintype "passive"))
    )
    (net (code "59") (name "Net-(VT6-B)") (class "Default")
      (node (ref "R26") (pin "2") (pinfunction "2_2") (pintype "passive"))
      (node (ref "VT6") (pin "1") (pinfunction "B_1") (pintype "passive"))
    )
    (net (code "60") (name "Net-(VT7-B)") (class "Default")
      (node (ref "R27") (pin "2") (pinfunction "2_2") (pintype "passive"))
      (node (ref "VT7") (pin "1") (pinfunction "B_1") (pintype "passive"))
    )
    (net (code "61") (name "Net-(VT8-B)") (class "Default")
      (node (ref "R13") (pin "2") (pinfunction "2_2") (pintype "passive"))
      (node (ref "VT8") (pin "1") (pinfunction "B_1") (pintype "passive"))
    )
    (net (code "62") (name "Net-(VT8-C)") (class "Default")
      (node (ref "R17") (pin "1") (pinfunction "1_1") (pintype "passive"))
      (node (ref "VT8") (pin "3") (pinfunction "C_3") (pintype "passive"))
    )
    (net (code "63") (name "unconnected-(D1-ADC6-Pad19)") (class "Default")
      (node (ref "D1") (pin "19") (pinfunction "ADC6_19") (pintype "passive+no_connect"))
    )
    (net (code "64") (name "unconnected-(D1-ADC7-Pad22)") (class "Default")
      (node (ref "D1") (pin "22") (pinfunction "ADC7_22") (pintype "passive+no_connect"))
    )
    (net (code "65") (name "unconnected-(D1-AREF-Pad20)") (class "Default")
      (node (ref "D1") (pin "20") (pinfunction "AREF_20") (pintype "passive+no_connect"))
    )
    (net (code "66") (name "unconnected-(D1-PB2-Pad14)") (class "Default")
      (node (ref "D1") (pin "14") (pinfunction "PB2_14") (pintype "passive+no_connect"))
    )
    (net (code "67") (name "unconnected-(D1-PE0-Pad3)") (class "Default")
      (node (ref "D1") (pin "3") (pinfunction "PE0_3") (pintype "passive+no_connect"))
    )
    (net (code "68") (name "unconnected-(D1-PE1-Pad6)") (class "Default")
      (node (ref "D1") (pin "6") (pinfunction "PE1_6") (pintype "passive+no_connect"))
    )
    (net (code "69") (name "unconnected-(D12-EP-Pad9)") (class "Default")
      (node (ref "D12") (pin "9") (pinfunction "EP_9") (pintype "passive+no_connect"))
    )
    (net (code "70") (name "unconnected-(D12-NC-Pad2)") (class "Default")
      (node (ref "D12") (pin "2") (pinfunction "NC_2") (pintype "passive+no_connect"))
    )
    (net (code "71") (name "unconnected-(D12-NC-Pad4)") (class "Default")
      (node (ref "D12") (pin "4") (pinfunction "NC_4") (pintype "passive+no_connect"))
    )
    (net (code "72") (name "unconnected-(D12-NC-Pad5)") (class "Default")
      (node (ref "D12") (pin "5") (pinfunction "NC_5") (pintype "passive+no_connect"))
    )
    (net (code "73") (name "unconnected-(D13-GPIO17-Pad59)") (class "Default")
      (node (ref "D13") (pin "59") (pinfunction "GPIO17_59") (pintype "passive+no_connect"))
    )
    (net (code "74") (name "unconnected-(D13-GPIO46-Pad35)") (class "Default")
      (node (ref "D13") (pin "35") (pinfunction "GPIO46_35") (pintype "passive+no_connect"))
    )
    (net (code "75") (name "unconnected-(D13-GPIO47-Pad48)") (class "Default")
      (node (ref "D13") (pin "48") (pinfunction "GPIO47_48") (pintype "passive+no_connect"))
    )
    (net (code "76") (name "unconnected-(D13-GPIO48-Pad49)") (class "Default")
      (node (ref "D13") (pin "49") (pinfunction "GPIO48_49") (pintype "passive+no_connect"))
    )
    (net (code "77") (name "unconnected-(D13-GPIO51-Pad38)") (class "Default")
      (node (ref "D13") (pin "38") (pinfunction "GPIO51_38") (pintype "passive+no_connect"))
    )
    (net (code "78") (name "unconnected-(D13-GPIO52-Pad37)") (class "Default")
      (node (ref "D13") (pin "37") (pinfunction "GPIO52_37") (pintype "passive+no_connect"))
    )
    (net (code "79") (name "unconnected-(D13-GPIO53-Pad31)") (class "Default")
      (node (ref "D13") (pin "31") (pinfunction "GPIO53_31") (pintype "passive"))
    )
    (net (code "80") (name "unconnected-(D13-I2C_SCL-Pad34)") (class "Default")
      (node (ref "D13") (pin "34") (pinfunction "I2C_SCL_34") (pintype "passive+no_connect"))
    )
    (net (code "81") (name "unconnected-(D13-I2C_SDA-Pad33)") (class "Default")
      (node (ref "D13") (pin "33") (pinfunction "I2C_SDA_33") (pintype "passive+no_connect"))
    )
    (net (code "82") (name "unconnected-(D13-LPRDB-Pad23)") (class "Default")
      (node (ref "D13") (pin "23") (pinfunction "LPRDB_23") (pintype "passive+no_connect"))
    )
    (net (code "83") (name "unconnected-(D13-NC-Pad25)") (class "Default")
      (node (ref "D13") (pin "25") (pinfunction "NC_25") (pintype "passive+no_connect"))
    )
    (net (code "84") (name "unconnected-(D13-NC-Pad26)") (class "Default")
      (node (ref "D13") (pin "26") (pinfunction "NC_26") (pintype "passive+no_connect"))
    )
    (net (code "85") (name "unconnected-(D13-NC-Pad27)") (class "Default")
      (node (ref "D13") (pin "27") (pinfunction "NC_27") (pintype "passive+no_connect"))
    )
    (net (code "86") (name "unconnected-(D13-NC-Pad28)") (class "Default")
      (node (ref "D13") (pin "28") (pinfunction "NC_28") (pintype "passive+no_connect"))
    )
    (net (code "87") (name "unconnected-(D13-NC-Pad29)") (class "Default")
      (node (ref "D13") (pin "29") (pinfunction "NC_29") (pintype "passive+no_connect"))
    )
    (net (code "88") (name "unconnected-(D13-NC-Pad60)") (class "Default")
      (node (ref "D13") (pin "60") (pinfunction "NC_60") (pintype "passive+no_connect"))
    )
    (net (code "89") (name "unconnected-(D13-NC-Pad61)") (class "Default")
      (node (ref "D13") (pin "61") (pinfunction "NC_61") (pintype "passive+no_connect"))
    )
    (net (code "90") (name "unconnected-(D13-NETLIGHT-Pad36)") (class "Default")
      (node (ref "D13") (pin "36") (pinfunction "NETLIGHT_36") (pintype "passive+no_connect"))
    )
    (net (code "91") (name "unconnected-(D13-PCM_CLK-Pad13)") (class "Default")
      (node (ref "D13") (pin "13") (pinfunction "PCM_CLK_13") (pintype "passive+no_connect"))
    )
    (net (code "92") (name "unconnected-(D13-PCM_IN-Pad15)") (class "Default")
      (node (ref "D13") (pin "15") (pinfunction "PCM_IN_15") (pintype "passive+no_connect"))
    )
    (net (code "93") (name "unconnected-(D13-PCM_OUT-Pad16)") (class "Default")
      (node (ref "D13") (pin "16") (pinfunction "PCM_OUT_16") (pintype "passive+no_connect"))
    )
    (net (code "94") (name "unconnected-(D13-PCM_SYNC-Pad14)") (class "Default")
      (node (ref "D13") (pin "14") (pinfunction "PCM_SYNC_14") (pintype "passive+no_connect"))
    )
    (net (code "95") (name "unconnected-(D13-TX_EN-Pad58)") (class "Default")
      (node (ref "D13") (pin "58") (pinfunction "TX_EN_58") (pintype "passive+no_connect"))
    )
    (net (code "96") (name "unconnected-(D13-U1RXD-Pad18)") (class "Default")
      (node (ref "D13") (pin "18") (pinfunction "U1RXD_18") (pintype "passive+no_connect"))
    )
    (net (code "97") (name "unconnected-(D13-U1TXD-Pad19)") (class "Default")
      (node (ref "D13") (pin "19") (pinfunction "U1TXD_19") (pintype "passive+no_connect"))
    )
    (net (code "98") (name "unconnected-(D13-UART0_DCD-Pad54)") (class "Default")
      (node (ref "D13") (pin "54") (pinfunction "UART0_DCD_54") (pintype "passive+no_connect"))
    )
    (net (code "99") (name "unconnected-(D13-UART0_DTR-Pad56)") (class "Default")
      (node (ref "D13") (pin "56") (pinfunction "UART0_DTR_56") (pintype "passive+no_connect"))
    )
    (net (code "100") (name "unconnected-(D13-UART0_RI-Pad53)") (class "Default")
      (node (ref "D13") (pin "53") (pinfunction "UART0_RI_53") (pintype "passive+no_connect"))
    )
    (net (code "101") (name "unconnected-(D13-USB_DM-Pad5)") (class "Default")
      (node (ref "D13") (pin "5") (pinfunction "USB_DM_5") (pintype "passive+no_connect"))
    )
    (net (code "102") (name "unconnected-(D13-USB_DP-Pad6)") (class "Default")
      (node (ref "D13") (pin "6") (pinfunction "USB_DP_6") (pintype "passive+no_connect"))
    )
    (net (code "103") (name "unconnected-(D13-VIO18_PMU-Pad24)") (class "Default")
      (node (ref "D13") (pin "24") (pinfunction "VIO18_PMU_24") (pintype "passive+no_connect"))
    )
    (net (code "104") (name "unconnected-(D13-WAKEIN-Pad21)") (class "Default")
      (node (ref "D13") (pin "21") (pinfunction "WAKEIN_21") (pintype "passive"))
    )
    (net (code "105") (name "unconnected-(D14-1PPS-Pad6)") (class "Default")
      (node (ref "D14") (pin "6") (pinfunction "1PPS_6") (pintype "passive"))
    )
    (net (code "106") (name "unconnected-(D14-ACT_SLP-Pad8)") (class "Default")
      (node (ref "D14") (pin "8") (pinfunction "ACT_SLP_8") (pintype "passive"))
    )
    (net (code "107") (name "unconnected-(D14-NC-Pad7)") (class "Default")
      (node (ref "D14") (pin "7") (pinfunction "NC_7") (pintype "passive"))
    )
    (net (code "108") (name "unconnected-(D14-NC-Pad10)") (class "Default")
      (node (ref "D14") (pin "10") (pinfunction "NC_10") (pintype "passive"))
    )
    (net (code "109") (name "unconnected-(D14-NC-Pad15)") (class "Default")
      (node (ref "D14") (pin "15") (pinfunction "NC_15") (pintype "passive"))
    )
    (net (code "110") (name "unconnected-(D14-NC-Pad16)") (class "Default")
      (node (ref "D14") (pin "16") (pinfunction "NC_16") (pintype "passive"))
    )
    (net (code "111") (name "unconnected-(D14-NRESET-Pad19)") (class "Default")
      (node (ref "D14") (pin "19") (pinfunction "NRESET_19") (pintype "passive"))
    )
    (net (code "112") (name "unconnected-(D14-ON_OFF-Pad22)") (class "Default")
      (node (ref "D14") (pin "22") (pinfunction "ON_OFF_22") (pintype "passive"))
    )
    (net (code "113") (name "unconnected-(D14-RX0-Pad13)") (class "Default")
      (node (ref "D14") (pin "13") (pinfunction "RX0_13") (pintype "passive"))
    )
    (net (code "114") (name "unconnected-(D14-STATUS-Pad9)") (class "Default")
      (node (ref "D14") (pin "9") (pinfunction "STATUS_9") (pintype "passive"))
    )
    (net (code "115") (name "unconnected-(D14-TX0-Pad14)") (class "Default")
      (node (ref "D14") (pin "14") (pinfunction "TX0_14") (pintype "passive"))
    )
    (net (code "116") (name "unconnected-(D14-WAKE-Pad5)") (class "Default")
      (node (ref "D14") (pin "5") (pinfunction "WAKE_5") (pintype "passive"))
    )
    (net (code "117") (name "unconnected-(J1-PadC6)") (class "Default")
      (node (ref "J1") (pin "C6") (pinfunction "C6_C6") (pintype "passive+no_connect"))
    )
  )
)
